# Microcontroller.net
KiCad netlist of a schematic drawn in Altium Designer
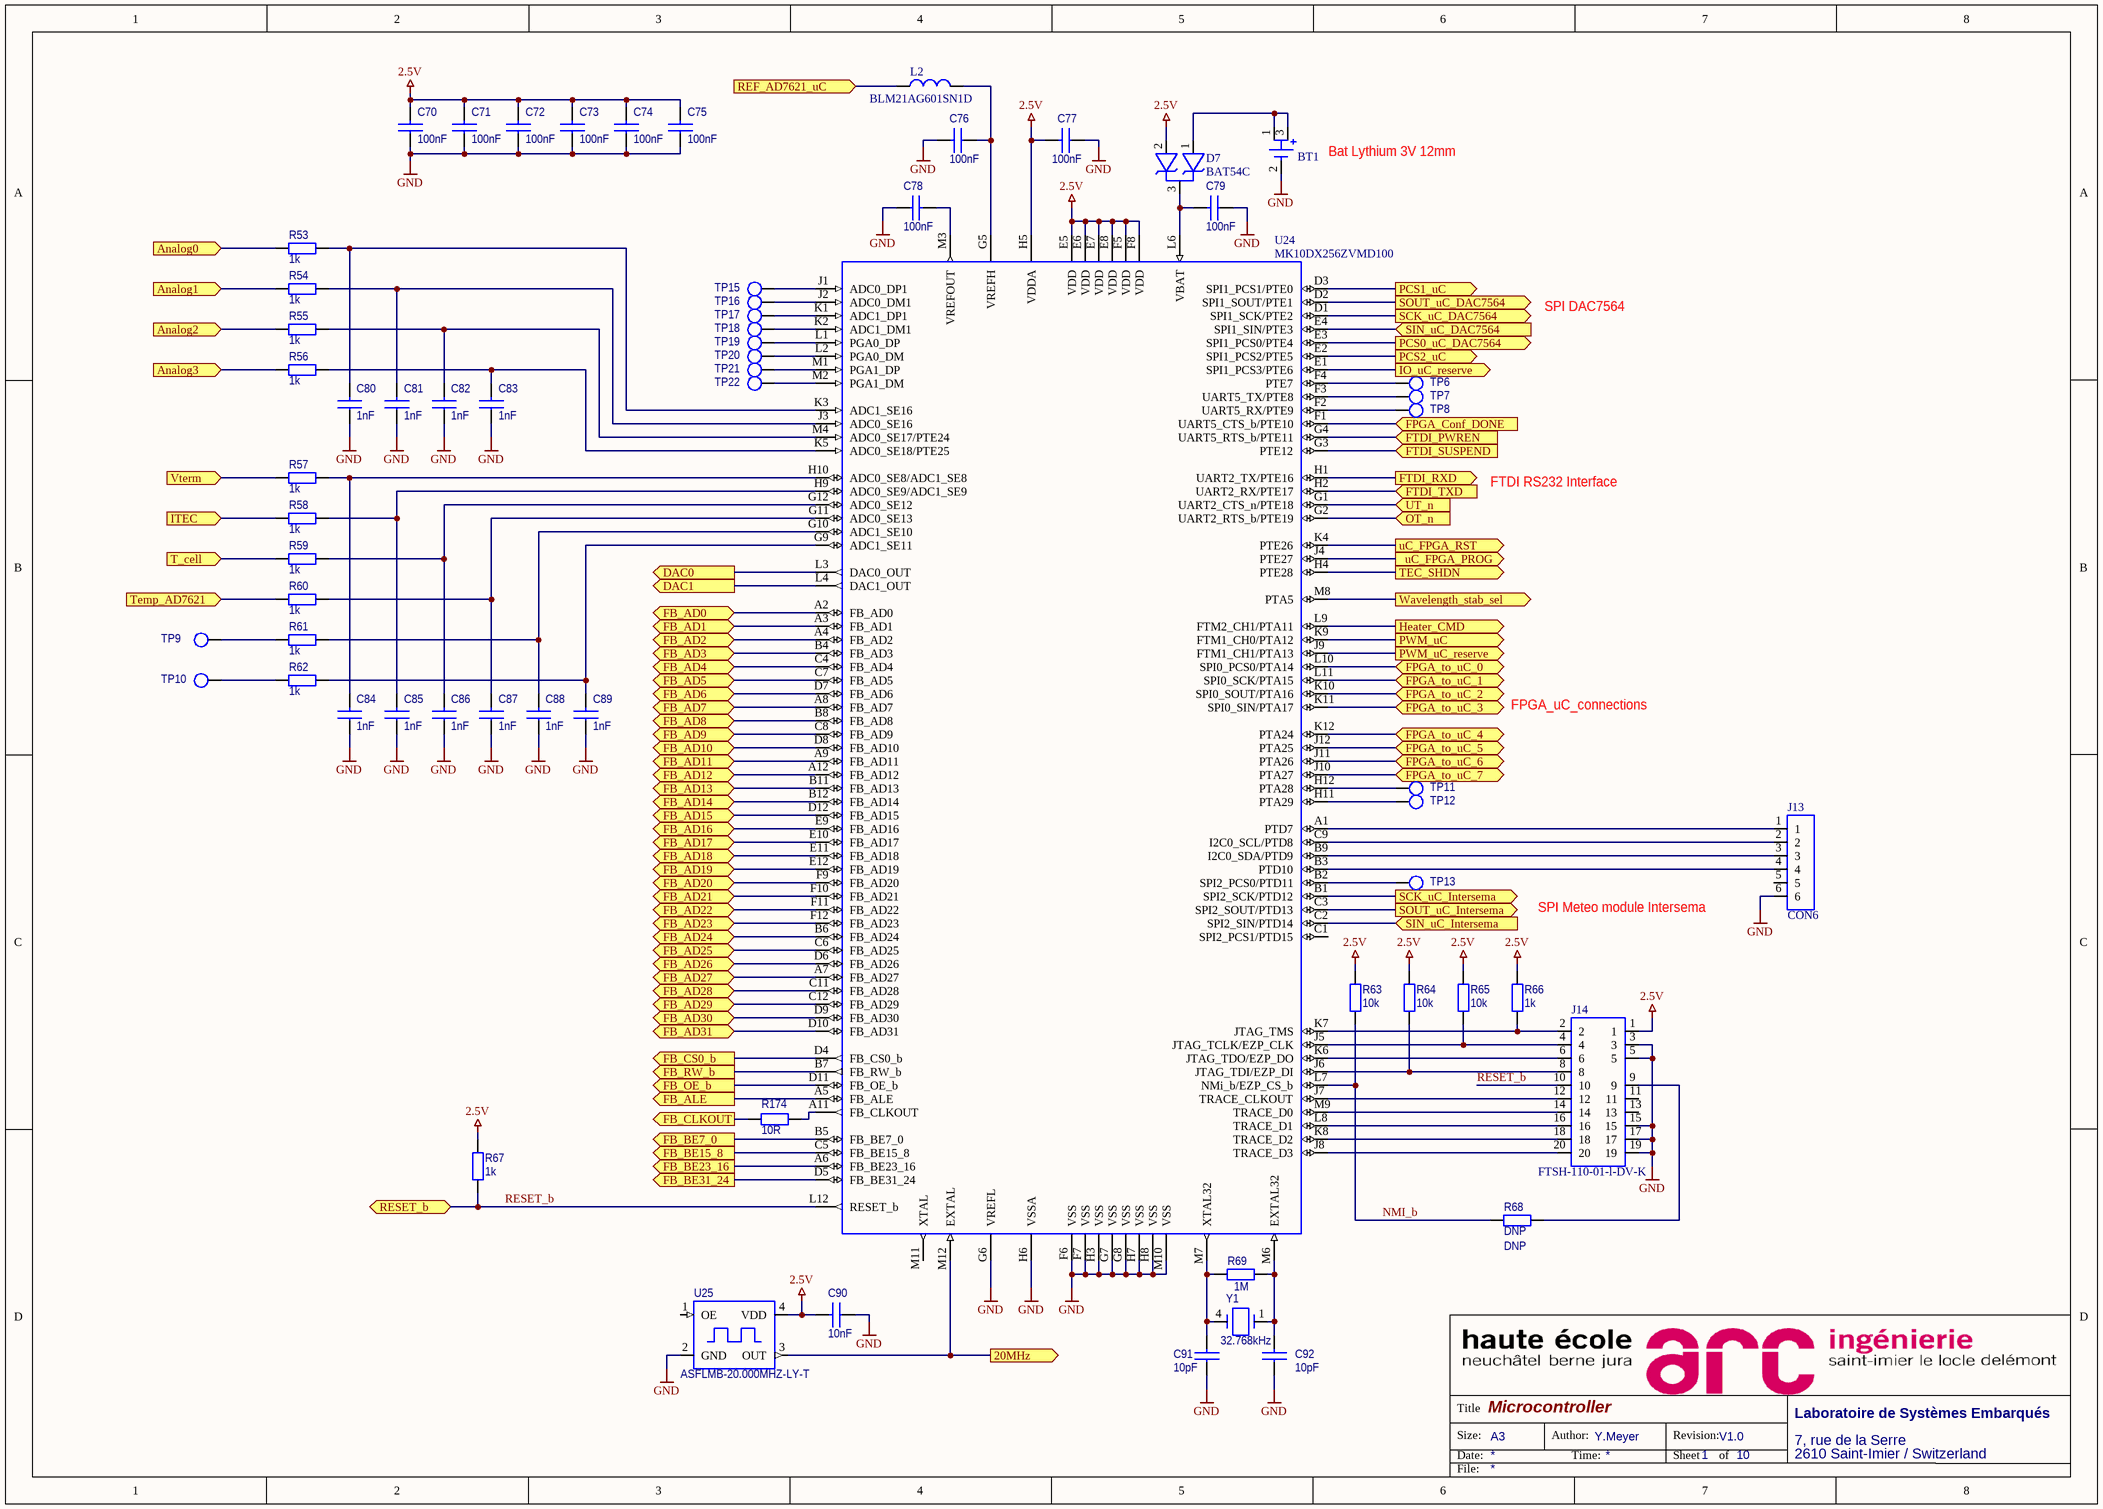
[diagram p0: Microcontroller.SchDoc]

(export (version "E")
  (design (tool "Eeschema 10.0.6"))
  (components
    (comp (ref "BT1")
      (value "3000TR")
      (footprint "3000TR")
      (description "HOLDER BATTERY COIN 12MM DIA SMD")
      (fields (field (name "MANUFACTURER") "Keystone Electronics"))
      (libsource (lib "EISI") (part "BAT_1"))
    )
    (comp (ref "C70")
      (value "100nF")
      (footprint "060301")
      (description "CAP CER 0.1UF 25V 10% X7R 0603")
      (fields (field (name "MANUFACTURER") "TDK Corporation") (field (name "VOLTAGE") "25V"))
      (libsource (lib "EISI") (part "CAPA"))
    )
    (comp (ref "C71")
      (value "100nF")
      (footprint "060301")
      (description "CAP CER 0.1UF 25V 10% X7R 0603")
      (fields (field (name "MANUFACTURER") "TDK Corporation") (field (name "VOLTAGE") "25V"))
      (libsource (lib "EISI") (part "CAPA"))
    )
    (comp (ref "C72")
      (value "100nF")
      (footprint "060301")
      (description "CAP CER 0.1UF 25V 10% X7R 0603")
      (fields (field (name "MANUFACTURER") "TDK Corporation") (field (name "VOLTAGE") "25V"))
      (libsource (lib "EISI") (part "CAPA"))
    )
    (comp (ref "C73")
      (value "100nF")
      (footprint "060301")
      (description "CAP CER 0.1UF 25V 10% X7R 0603")
      (fields (field (name "MANUFACTURER") "TDK Corporation") (field (name "VOLTAGE") "25V"))
      (libsource (lib "EISI") (part "CAPA"))
    )
    (comp (ref "C74")
      (value "100nF")
      (footprint "060301")
      (description "CAP CER 0.1UF 25V 10% X7R 0603")
      (fields (field (name "MANUFACTURER") "TDK Corporation") (field (name "VOLTAGE") "25V"))
      (libsource (lib "EISI") (part "CAPA"))
    )
    (comp (ref "C75")
      (value "100nF")
      (footprint "060301")
      (description "CAP CER 0.1UF 25V 10% X7R 0603")
      (fields (field (name "MANUFACTURER") "TDK Corporation") (field (name "VOLTAGE") "25V"))
      (libsource (lib "EISI") (part "CAPA"))
    )
    (comp (ref "C76")
      (value "100nF")
      (footprint "060301")
      (description "CAP CER 0.1UF 25V 10% X7R 0603")
      (fields (field (name "MANUFACTURER") "TDK Corporation") (field (name "VOLTAGE") "25V"))
      (libsource (lib "EISI") (part "CAPA"))
    )
    (comp (ref "C77")
      (value "100nF")
      (footprint "060301")
      (description "CAP CER 0.1UF 25V 10% X7R 0603")
      (fields (field (name "MANUFACTURER") "TDK Corporation") (field (name "VOLTAGE") "25V"))
      (libsource (lib "EISI") (part "CAPA"))
    )
    (comp (ref "C78")
      (value "100nF")
      (footprint "060301")
      (description "CAP CER 0.1UF 25V 10% X7R 0603")
      (fields (field (name "MANUFACTURER") "TDK Corporation") (field (name "VOLTAGE") "25V"))
      (libsource (lib "EISI") (part "CAPA"))
    )
    (comp (ref "C79")
      (value "100nF")
      (footprint "060301")
      (description "CAP CER 0.1UF 25V 10% X7R 0603")
      (fields (field (name "MANUFACTURER") "TDK Corporation") (field (name "VOLTAGE") "25V"))
      (libsource (lib "EISI") (part "CAPA"))
    )
    (comp (ref "C80")
      (value "1nF")
      (footprint "060301")
      (description "CAP CER 1000PF 50V 10% X7R 0603")
      (fields (field (name "MANUFACTURER") "Murata"))
      (libsource (lib "EISI") (part "CAPA"))
    )
    (comp (ref "C81")
      (value "1nF")
      (footprint "060301")
      (description "CAP CER 1000PF 50V 10% X7R 0603")
      (fields (field (name "MANUFACTURER") "Murata"))
      (libsource (lib "EISI") (part "CAPA"))
    )
    (comp (ref "C82")
      (value "1nF")
      (footprint "060301")
      (description "CAP CER 1000PF 50V 10% X7R 0603")
      (fields (field (name "MANUFACTURER") "Murata"))
      (libsource (lib "EISI") (part "CAPA"))
    )
    (comp (ref "C83")
      (value "1nF")
      (footprint "060301")
      (description "CAP CER 1000PF 50V 10% X7R 0603")
      (fields (field (name "MANUFACTURER") "Murata"))
      (libsource (lib "EISI") (part "CAPA"))
    )
    (comp (ref "C84")
      (value "1nF")
      (footprint "060301")
      (description "CAP CER 1000PF 50V 10% X7R 0603")
      (fields (field (name "MANUFACTURER") "Murata"))
      (libsource (lib "EISI") (part "CAPA"))
    )
    (comp (ref "C85")
      (value "1nF")
      (footprint "060301")
      (description "CAP CER 1000PF 50V 10% X7R 0603")
      (fields (field (name "MANUFACTURER") "Murata"))
      (libsource (lib "EISI") (part "CAPA"))
    )
    (comp (ref "C86")
      (value "1nF")
      (footprint "060301")
      (description "CAP CER 1000PF 50V 10% X7R 0603")
      (fields (field (name "MANUFACTURER") "Murata"))
      (libsource (lib "EISI") (part "CAPA"))
    )
    (comp (ref "C87")
      (value "1nF")
      (footprint "060301")
      (description "CAP CER 1000PF 50V 10% X7R 0603")
      (fields (field (name "MANUFACTURER") "Murata"))
      (libsource (lib "EISI") (part "CAPA"))
    )
    (comp (ref "C88")
      (value "1nF")
      (footprint "060301")
      (description "CAP CER 1000PF 50V 10% X7R 0603")
      (fields (field (name "MANUFACTURER") "Murata"))
      (libsource (lib "EISI") (part "CAPA"))
    )
    (comp (ref "C89")
      (value "1nF")
      (footprint "060301")
      (description "CAP CER 1000PF 50V 10% X7R 0603")
      (fields (field (name "MANUFACTURER") "Murata"))
      (libsource (lib "EISI") (part "CAPA"))
    )
    (comp (ref "C90")
      (value "10nF")
      (footprint "060301")
      (description "CAP CER 10000PF 50V 10% X7R 0")
      (fields (field (name "MANUFACTURER") "EPCOS Inc"))
      (libsource (lib "EISI") (part "CAPA"))
    )
    (comp (ref "C91")
      (value "10pF")
      (footprint "060301")
      (description "CAP CER 10PF 50V 5% NP0 0603")
      (fields (field (name "VOLTAGE") "50V") (field (name "MANUFACTURER") "Kemet"))
      (libsource (lib "EISI") (part "CAPA"))
    )
    (comp (ref "C92")
      (value "10pF")
      (footprint "060301")
      (description "CAP CER 10PF 50V 5% NP0 0603")
      (fields (field (name "VOLTAGE") "50V") (field (name "MANUFACTURER") "Kemet"))
      (libsource (lib "EISI") (part "CAPA"))
    )
    (comp (ref "D7")
      (value "BAT54C")
      (footprint "SOT2301")
      (description "DIODE SCHTTKY CC 200MA 30V SOT23")
      (fields (field (name "MANUFACTURER") "Comchip Technology"))
      (libsource (lib "EISI") (part "BAT54C"))
    )
    (comp (ref "J13")
      (value "CON6")
      (footprint "J106A101")
      (description "Barette 6 pin")
      (libsource (lib "EISI") (part "CON6"))
    )
    (comp (ref "J14")
      (value "FTSH-110-01-l-DV-K")
      (footprint "FTSH-110-01-X-DV-EJ")
      (description "CONN UNSHROUDED HDR 20POS .05\"")
      (fields (field (name "MANUFACTURER") "Samtec Inc"))
      (libsource (lib "EISI") (part "CON20_JTAG"))
    )
    (comp (ref "L2")
      (value "BLM21AG601SN1D")
      (footprint "080501")
      (description "FERRITE CHIP 600 OHM 200MA 0805")
      (fields (field (name "MANUFACTURER") "Murata Electronics"))
      (libsource (lib "EISI") (part "Ferrite Bead"))
    )
    (comp (ref "R53")
      (value "1k")
      (footprint "060301")
      (description "RES 1.00K OHM 1/10W 1% 0603 SMD")
      (fields (field (name "MANUFACTURER") "Yageo"))
      (libsource (lib "EISI") (part "RES"))
    )
    (comp (ref "R54")
      (value "1k")
      (footprint "060301")
      (description "RES 1.00K OHM 1/10W 1% 0603 SMD")
      (fields (field (name "MANUFACTURER") "Yageo"))
      (libsource (lib "EISI") (part "RES"))
    )
    (comp (ref "R55")
      (value "1k")
      (footprint "060301")
      (description "RES 1.00K OHM 1/10W 1% 0603 SMD")
      (fields (field (name "MANUFACTURER") "Yageo"))
      (libsource (lib "EISI") (part "RES"))
    )
    (comp (ref "R56")
      (value "1k")
      (footprint "060301")
      (description "RES 1.00K OHM 1/10W 1% 0603 SMD")
      (fields (field (name "MANUFACTURER") "Yageo"))
      (libsource (lib "EISI") (part "RES"))
    )
    (comp (ref "R57")
      (value "1k")
      (footprint "060301")
      (description "RES 1.00K OHM 1/10W 1% 0603 SMD")
      (fields (field (name "MANUFACTURER") "Yageo"))
      (libsource (lib "EISI") (part "RES"))
    )
    (comp (ref "R58")
      (value "1k")
      (footprint "060301")
      (description "RES 1.00K OHM 1/10W 1% 0603 SMD")
      (fields (field (name "MANUFACTURER") "Yageo"))
      (libsource (lib "EISI") (part "RES"))
    )
    (comp (ref "R59")
      (value "1k")
      (footprint "060301")
      (description "RES 1.00K OHM 1/10W 1% 0603 SMD")
      (fields (field (name "MANUFACTURER") "Yageo"))
      (libsource (lib "EISI") (part "RES"))
    )
    (comp (ref "R60")
      (value "1k")
      (footprint "060301")
      (description "RES 1.00K OHM 1/10W 1% 0603 SMD")
      (fields (field (name "MANUFACTURER") "Yageo"))
      (libsource (lib "EISI") (part "RES"))
    )
    (comp (ref "R61")
      (value "1k")
      (footprint "060301")
      (description "RES 1.00K OHM 1/10W 1% 0603 SMD")
      (fields (field (name "MANUFACTURER") "Yageo"))
      (libsource (lib "EISI") (part "RES"))
    )
    (comp (ref "R62")
      (value "1k")
      (footprint "060301")
      (description "RES 1.00K OHM 1/10W 1% 0603 SMD")
      (fields (field (name "MANUFACTURER") "Yageo"))
      (libsource (lib "EISI") (part "RES"))
    )
    (comp (ref "R63")
      (value "10k")
      (footprint "060301")
      (description "RES 10.0K OHM 1/10W 1% 0603 SMD")
      (fields (field (name "MANUFACTURER") "Yageo"))
      (libsource (lib "") (part "RES_1"))
    )
    (comp (ref "R64")
      (value "10k")
      (footprint "060301")
      (description "RES 10.0K OHM 1/10W 1% 0603 SMD")
      (fields (field (name "MANUFACTURER") "Yageo"))
      (libsource (lib "") (part "RES_1"))
    )
    (comp (ref "R65")
      (value "10k")
      (footprint "060301")
      (description "RES 10.0K OHM 1/10W 1% 0603 SMD")
      (fields (field (name "MANUFACTURER") "Yageo"))
      (libsource (lib "") (part "RES_1"))
    )
    (comp (ref "R66")
      (value "1k")
      (footprint "060301")
      (description "RES 1.00K OHM 1/10W 1% 0603 SMD")
      (fields (field (name "MANUFACTURER") "Yageo"))
      (libsource (lib "") (part "RES_1"))
    )
    (comp (ref "R67")
      (value "1k")
      (footprint "060301")
      (description "RES 1.00K OHM 1/10W 1% 0603 SMD")
      (fields (field (name "MANUFACTURER") "Yageo"))
      (libsource (lib "") (part "RES_1"))
    )
    (comp (ref "R68")
      (value "DNP")
      (footprint "060301")
      (description "RES 0.0 OHM 1/10W 0603 SMD")
      (fields (field (name "DNP") "DNP") (field (name "MANUFACTURER") "Yageo"))
      (libsource (lib "EISI") (part "RES"))
    )
    (comp (ref "R69")
      (value "1M")
      (footprint "060301")
      (description "RES 1.00M OHM 1/10W 1% 0603 SMD")
      (fields (field (name "MANUFACTURER") "Yageo"))
      (libsource (lib "EISI") (part "RES"))
    )
    (comp (ref "R174")
      (value "10R")
      (footprint "060301")
      (description "RES 10.0 OHM 1/10W 1% 0603 SMD")
      (fields (field (name "MANUFACTURER") "Yageo"))
      (libsource (lib "EISI") (part "RES"))
    )
    (comp (ref "TP6") (value "Test point") (footprint "TP_SMD_06mm") (libsource (lib "EISI") (part "TP")))
    (comp (ref "TP7") (value "Test point") (footprint "TP_SMD_06mm") (libsource (lib "EISI") (part "TP")))
    (comp (ref "TP8") (value "Test point") (footprint "TP_SMD_06mm") (libsource (lib "EISI") (part "TP")))
    (comp (ref "TP9") (value "Test point") (footprint "TP_SMD_06mm") (libsource (lib "EISI") (part "TP")))
    (comp (ref "TP10") (value "Test point") (footprint "TP_SMD_06mm") (libsource (lib "EISI") (part "TP")))
    (comp (ref "TP11") (value "Test point") (footprint "TP_SMD_06mm") (libsource (lib "EISI") (part "TP")))
    (comp (ref "TP12") (value "Test point") (footprint "TP_SMD_06mm") (libsource (lib "EISI") (part "TP")))
    (comp (ref "TP13") (value "Test point") (footprint "TP_SMD_06mm") (libsource (lib "EISI") (part "TP")))
    (comp (ref "TP15") (value "Test point") (footprint "TP_SMD_06mm") (libsource (lib "EISI") (part "TP")))
    (comp (ref "TP16") (value "Test point") (footprint "TP_SMD_06mm") (libsource (lib "EISI") (part "TP")))
    (comp (ref "TP17") (value "Test point") (footprint "TP_SMD_06mm") (libsource (lib "EISI") (part "TP")))
    (comp (ref "TP18") (value "Test point") (footprint "TP_SMD_06mm") (libsource (lib "EISI") (part "TP")))
    (comp (ref "TP19") (value "Test point") (footprint "TP_SMD_06mm") (libsource (lib "EISI") (part "TP")))
    (comp (ref "TP20") (value "Test point") (footprint "TP_SMD_06mm") (libsource (lib "EISI") (part "TP")))
    (comp (ref "TP21") (value "Test point") (footprint "TP_SMD_06mm") (libsource (lib "EISI") (part "TP")))
    (comp (ref "TP22") (value "Test point") (footprint "TP_SMD_06mm") (libsource (lib "EISI") (part "TP")))
    (comp (ref "U24")
      (value "MK10DX256ZVMD100")
      (footprint "MAPBGA144")
      (description "IC ARM CORTEX MCU 256K 144-MAP")
      (fields (field (name "MANUFACTURER") "Freescale Semiconductor"))
      (libsource (lib "EISI") (part "MK10X256VMD100"))
    )
    (comp (ref "U25")
      (value "ASFLMB-20.000MHZ-LY-T")
      (footprint "OSC05")
      (description "OSC MEMS 20.000 MHZ SMD")
      (fields (field (name "MANUFACTURER") "Abracon Corporation"))
      (libsource (lib "EISI") (part "Oscillateur"))
    )
    (comp (ref "Y1")
      (value "32.768kHz")
      (description "CRYSTAL 32.768 KHZ 12.5PF SMD")
      (fields (field (name "MANUFACTURER") "ECS Inc") (field (name "Comment") "ECS-.327-12.5-17X-C-TR"))
      (libsource (lib "*") (part "Crystal_32"))
    )
  )
  (nets
    (net (code "1") (name "/20MHz") (class "Default")
      (node (ref "U24") (pin "M12") (pinfunction "EXTAL_M12") (pintype "input"))
      (node (ref "U25") (pin "3") (pinfunction "OUT_3") (pintype "output"))
    )
    (net (code "2") (name "/Analog0") (class "Default")
      (node (ref "R53") (pin "1") (pinfunction "1_1") (pintype "passive"))
    )
    (net (code "3") (name "/Analog1") (class "Default")
      (node (ref "R54") (pin "1") (pinfunction "1_1") (pintype "passive"))
    )
    (net (code "4") (name "/Analog2") (class "Default")
      (node (ref "R55") (pin "1") (pinfunction "1_1") (pintype "passive"))
    )
    (net (code "5") (name "/Analog3") (class "Default")
      (node (ref "R56") (pin "1") (pinfunction "1_1") (pintype "passive"))
    )
    (net (code "6") (name "/DAC0") (class "Default")
      (node (ref "U24") (pin "L3") (pinfunction "DAC0_OUT_L3") (pintype "output"))
    )
    (net (code "7") (name "/DAC1") (class "Default")
      (node (ref "U24") (pin "L4") (pinfunction "DAC1_OUT_L4") (pintype "output"))
    )
    (net (code "8") (name "/FB_AD0") (class "Default")
      (node (ref "U24") (pin "A2") (pinfunction "FB_AD0_A2") (pintype "bidirectional"))
    )
    (net (code "9") (name "/FB_AD1") (class "Default")
      (node (ref "U24") (pin "A3") (pinfunction "FB_AD1_A3") (pintype "bidirectional"))
    )
    (net (code "10") (name "/FB_AD2") (class "Default")
      (node (ref "U24") (pin "A4") (pinfunction "FB_AD2_A4") (pintype "bidirectional"))
    )
    (net (code "11") (name "/FB_AD3") (class "Default")
      (node (ref "U24") (pin "B4") (pinfunction "FB_AD3_B4") (pintype "bidirectional"))
    )
    (net (code "12") (name "/FB_AD4") (class "Default")
      (node (ref "U24") (pin "C4") (pinfunction "FB_AD4_C4") (pintype "bidirectional"))
    )
    (net (code "13") (name "/FB_AD5") (class "Default")
      (node (ref "U24") (pin "C7") (pinfunction "FB_AD5_C7") (pintype "bidirectional"))
    )
    (net (code "14") (name "/FB_AD6") (class "Default")
      (node (ref "U24") (pin "D7") (pinfunction "FB_AD6_D7") (pintype "bidirectional"))
    )
    (net (code "15") (name "/FB_AD7") (class "Default")
      (node (ref "U24") (pin "A8") (pinfunction "FB_AD7_A8") (pintype "bidirectional"))
    )
    (net (code "16") (name "/FB_AD8") (class "Default")
      (node (ref "U24") (pin "B8") (pinfunction "FB_AD8_B8") (pintype "bidirectional"))
    )
    (net (code "17") (name "/FB_AD9") (class "Default")
      (node (ref "U24") (pin "C8") (pinfunction "FB_AD9_C8") (pintype "bidirectional"))
    )
    (net (code "18") (name "/FB_AD10") (class "Default")
      (node (ref "U24") (pin "D8") (pinfunction "FB_AD10_D8") (pintype "bidirectional"))
    )
    (net (code "19") (name "/FB_AD11") (class "Default")
      (node (ref "U24") (pin "A9") (pinfunction "FB_AD11_A9") (pintype "bidirectional"))
    )
    (net (code "20") (name "/FB_AD12") (class "Default")
      (node (ref "U24") (pin "A12") (pinfunction "FB_AD12_A12") (pintype "bidirectional"))
    )
    (net (code "21") (name "/FB_AD13") (class "Default")
      (node (ref "U24") (pin "B11") (pinfunction "FB_AD13_B11") (pintype "bidirectional"))
    )
    (net (code "22") (name "/FB_AD14") (class "Default")
      (node (ref "U24") (pin "B12") (pinfunction "FB_AD14_B12") (pintype "bidirectional"))
    )
    (net (code "23") (name "/FB_AD15") (class "Default")
      (node (ref "U24") (pin "D12") (pinfunction "FB_AD15_D12") (pintype "bidirectional"))
    )
    (net (code "24") (name "/FB_AD16") (class "Default")
      (node (ref "U24") (pin "E9") (pinfunction "FB_AD16_E9") (pintype "bidirectional"))
    )
    (net (code "25") (name "/FB_AD17") (class "Default")
      (node (ref "U24") (pin "E10") (pinfunction "FB_AD17_E10") (pintype "bidirectional"))
    )
    (net (code "26") (name "/FB_AD18") (class "Default")
      (node (ref "U24") (pin "E11") (pinfunction "FB_AD18_E11") (pintype "bidirectional"))
    )
    (net (code "27") (name "/FB_AD19") (class "Default")
      (node (ref "U24") (pin "E12") (pinfunction "FB_AD19_E12") (pintype "bidirectional"))
    )
    (net (code "28") (name "/FB_AD20") (class "Default")
      (node (ref "U24") (pin "F9") (pinfunction "FB_AD20_F9") (pintype "bidirectional"))
    )
    (net (code "29") (name "/FB_AD21") (class "Default")
      (node (ref "U24") (pin "F10") (pinfunction "FB_AD21_F10") (pintype "bidirectional"))
    )
    (net (code "30") (name "/FB_AD22") (class "Default")
      (node (ref "U24") (pin "F11") (pinfunction "FB_AD22_F11") (pintype "bidirectional"))
    )
    (net (code "31") (name "/FB_AD23") (class "Default")
      (node (ref "U24") (pin "F12") (pinfunction "FB_AD23_F12") (pintype "bidirectional"))
    )
    (net (code "32") (name "/FB_AD24") (class "Default")
      (node (ref "U24") (pin "B6") (pinfunction "FB_AD24_B6") (pintype "bidirectional"))
    )
    (net (code "33") (name "/FB_AD25") (class "Default")
      (node (ref "U24") (pin "C6") (pinfunction "FB_AD25_C6") (pintype "bidirectional"))
    )
    (net (code "34") (name "/FB_AD26") (class "Default")
      (node (ref "U24") (pin "D6") (pinfunction "FB_AD26_D6") (pintype "bidirectional"))
    )
    (net (code "35") (name "/FB_AD27") (class "Default")
      (node (ref "U24") (pin "A7") (pinfunction "FB_AD27_A7") (pintype "bidirectional"))
    )
    (net (code "36") (name "/FB_AD28") (class "Default")
      (node (ref "U24") (pin "C11") (pinfunction "FB_AD28_C11") (pintype "bidirectional"))
    )
    (net (code "37") (name "/FB_AD29") (class "Default")
      (node (ref "U24") (pin "C12") (pinfunction "FB_AD29_C12") (pintype "bidirectional"))
    )
    (net (code "38") (name "/FB_AD30") (class "Default")
      (node (ref "U24") (pin "D9") (pinfunction "FB_AD30_D9") (pintype "bidirectional"))
    )
    (net (code "39") (name "/FB_AD31") (class "Default")
      (node (ref "U24") (pin "D10") (pinfunction "FB_AD31_D10") (pintype "bidirectional"))
    )
    (net (code "40") (name "/FB_ALE") (class "Default")
      (node (ref "U24") (pin "A5") (pinfunction "FB_ALE_A5") (pintype "bidirectional"))
    )
    (net (code "41") (name "/FB_BE7_0") (class "Default")
      (node (ref "U24") (pin "B5") (pinfunction "FB_BE7_0_B5") (pintype "bidirectional"))
    )
    (net (code "42") (name "/FB_BE15_8") (class "Default")
      (node (ref "U24") (pin "C5") (pinfunction "FB_BE15_8_C5") (pintype "bidirectional"))
    )
    (net (code "43") (name "/FB_BE23_16") (class "Default")
      (node (ref "U24") (pin "A6") (pinfunction "FB_BE23_16_A6") (pintype "bidirectional"))
    )
    (net (code "44") (name "/FB_BE31_24") (class "Default")
      (node (ref "U24") (pin "D5") (pinfunction "FB_BE31_24_D5") (pintype "bidirectional"))
    )
    (net (code "45") (name "/FB_CLKOUT") (class "Default")
      (node (ref "R174") (pin "1") (pinfunction "1_1") (pintype "passive"))
    )
    (net (code "46") (name "/FB_CS0_b") (class "Default")
      (node (ref "U24") (pin "D4") (pinfunction "FB_CS0_b_D4") (pintype "output"))
    )
    (net (code "47") (name "/FB_OE_b") (class "Default")
      (node (ref "U24") (pin "D11") (pinfunction "FB_OE_b_D11") (pintype "bidirectional"))
    )
    (net (code "48") (name "/FB_RW_b") (class "Default")
      (node (ref "U24") (pin "B7") (pinfunction "FB_RW_b_B7") (pintype "output"))
    )
    (net (code "49") (name "/FPGA_Conf_DONE") (class "Default")
      (node (ref "U24") (pin "F1") (pinfunction "UART5_CTS_b/PTE10_F1") (pintype "bidirectional"))
    )
    (net (code "50") (name "/FPGA_to_uC_0") (class "Default")
      (node (ref "U24") (pin "L10") (pinfunction "SPI0_PCS0/PTA14_L10") (pintype "bidirectional"))
    )
    (net (code "51") (name "/FPGA_to_uC_1") (class "Default")
      (node (ref "U24") (pin "L11") (pinfunction "SPI0_SCK/PTA15_L11") (pintype "bidirectional"))
    )
    (net (code "52") (name "/FPGA_to_uC_2") (class "Default")
      (node (ref "U24") (pin "K10") (pinfunction "SPI0_SOUT/PTA16_K10") (pintype "bidirectional"))
    )
    (net (code "53") (name "/FPGA_to_uC_3") (class "Default")
      (node (ref "U24") (pin "K11") (pinfunction "SPI0_SIN/PTA17_K11") (pintype "bidirectional"))
    )
    (net (code "54") (name "/FPGA_to_uC_4") (class "Default")
      (node (ref "U24") (pin "K12") (pinfunction "PTA24_K12") (pintype "bidirectional"))
    )
    (net (code "55") (name "/FPGA_to_uC_5") (class "Default")
      (node (ref "U24") (pin "J12") (pinfunction "PTA25_J12") (pintype "bidirectional"))
    )
    (net (code "56") (name "/FPGA_to_uC_6") (class "Default")
      (node (ref "U24") (pin "J11") (pinfunction "PTA26_J11") (pintype "bidirectional"))
    )
    (net (code "57") (name "/FPGA_to_uC_7") (class "Default")
      (node (ref "U24") (pin "J10") (pinfunction "PTA27_J10") (pintype "bidirectional"))
    )
    (net (code "58") (name "/FTDI_PWREN") (class "Default")
      (node (ref "U24") (pin "G4") (pinfunction "UART5_RTS_b/PTE11_G4") (pintype "bidirectional"))
    )
    (net (code "59") (name "/FTDI_RXD") (class "Default")
      (node (ref "U24") (pin "H1") (pinfunction "UART2_TX/PTE16_H1") (pintype "bidirectional"))
    )
    (net (code "60") (name "/FTDI_SUSPEND") (class "Default")
      (node (ref "U24") (pin "G3") (pinfunction "PTE12_G3") (pintype "bidirectional"))
    )
    (net (code "61") (name "/FTDI_TXD") (class "Default")
      (node (ref "U24") (pin "H2") (pinfunction "UART2_RX/PTE17_H2") (pintype "bidirectional"))
    )
    (net (code "62") (name "/Heater_CMD") (class "Default")
      (node (ref "U24") (pin "L9") (pinfunction "FTM2_CH1/PTA11_L9") (pintype "bidirectional"))
    )
    (net (code "63") (name "/IO_uC_reserve") (class "Default")
      (node (ref "U24") (pin "E1") (pinfunction "SPI1_PCS3/PTE6_E1") (pintype "bidirectional"))
    )
    (net (code "64") (name "/ITEC") (class "Default")
      (node (ref "R58") (pin "1") (pinfunction "1_1") (pintype "passive"))
    )
    (net (code "65") (name "/NMI_b") (class "Default")
      (node (ref "R63") (pin "2") (pinfunction "2_2") (pintype "passive"))
      (node (ref "R68") (pin "1") (pinfunction "1_1") (pintype "passive"))
      (node (ref "U24") (pin "L7") (pinfunction "NMi_b/EZP_CS_b_L7") (pintype "bidirectional"))
    )
    (net (code "66") (name "/OT_n") (class "Default")
      (node (ref "U24") (pin "G2") (pinfunction "UART2_RTS_b/PTE19_G2") (pintype "bidirectional"))
    )
    (net (code "67") (name "/PCS0_uC_DAC7564") (class "Default")
      (node (ref "U24") (pin "E3") (pinfunction "SPI1_PCS0/PTE4_E3") (pintype "bidirectional"))
    )
    (net (code "68") (name "/PCS1_uC") (class "Default")
      (node (ref "U24") (pin "D3") (pinfunction "SPI1_PCS1/PTE0_D3") (pintype "bidirectional"))
    )
    (net (code "69") (name "/PCS2_uC") (class "Default")
      (node (ref "U24") (pin "E2") (pinfunction "SPI1_PCS2/PTE5_E2") (pintype "bidirectional"))
    )
    (net (code "70") (name "/PWM_uC") (class "Default")
      (node (ref "U24") (pin "K9") (pinfunction "FTM1_CH0/PTA12_K9") (pintype "bidirectional"))
    )
    (net (code "71") (name "/PWM_uC_reserve") (class "Default")
      (node (ref "U24") (pin "J9") (pinfunction "FTM1_CH1/PTA13_J9") (pintype "bidirectional"))
    )
    (net (code "72") (name "/REF_AD7621_uC") (class "Default")
      (node (ref "L2") (pin "1") (pinfunction "1_1") (pintype "passive"))
    )
    (net (code "73") (name "/RESET_b") (class "Default")
      (node (ref "J14") (pin "10") (pinfunction "10_10") (pintype "passive"))
      (node (ref "R67") (pin "2") (pinfunction "2_2") (pintype "passive"))
      (node (ref "U24") (pin "L12") (pinfunction "RESET_b_L12") (pintype "output"))
    )
    (net (code "74") (name "/SCK_uC_DAC7564") (class "Default")
      (node (ref "U24") (pin "D1") (pinfunction "SPI1_SCK/PTE2_D1") (pintype "bidirectional"))
    )
    (net (code "75") (name "/SCK_uC_Intersema") (class "Default")
      (node (ref "U24") (pin "B1") (pinfunction "SPI2_SCK/PTD12_B1") (pintype "bidirectional"))
    )
    (net (code "76") (name "/SIN_uC_DAC7564") (class "Default")
      (node (ref "U24") (pin "E4") (pinfunction "SPI1_SIN/PTE3_E4") (pintype "bidirectional"))
    )
    (net (code "77") (name "/SIN_uC_Intersema") (class "Default")
      (node (ref "U24") (pin "C2") (pinfunction "SPI2_SIN/PTD14_C2") (pintype "bidirectional"))
    )
    (net (code "78") (name "/SOUT_uC_DAC7564") (class "Default")
      (node (ref "U24") (pin "D2") (pinfunction "SPI1_SOUT/PTE1_D2") (pintype "bidirectional"))
    )
    (net (code "79") (name "/SOUT_uC_Intersema") (class "Default")
      (node (ref "U24") (pin "C3") (pinfunction "SPI2_SOUT/PTD13_C3") (pintype "bidirectional"))
    )
    (net (code "80") (name "/TEC_SHDN") (class "Default")
      (node (ref "U24") (pin "H4") (pinfunction "PTE28_H4") (pintype "bidirectional"))
    )
    (net (code "81") (name "/T_cell") (class "Default")
      (node (ref "R59") (pin "1") (pinfunction "1_1") (pintype "passive"))
    )
    (net (code "82") (name "/Temp_AD7621") (class "Default")
      (node (ref "R60") (pin "1") (pinfunction "1_1") (pintype "passive"))
    )
    (net (code "83") (name "/UT_n") (class "Default")
      (node (ref "U24") (pin "G1") (pinfunction "UART2_CTS_n/PTE18_G1") (pintype "bidirectional"))
    )
    (net (code "84") (name "/Vterm") (class "Default")
      (node (ref "R57") (pin "1") (pinfunction "1_1") (pintype "passive"))
    )
    (net (code "85") (name "/Wavelength_stab_sel") (class "Default")
      (node (ref "U24") (pin "M8") (pinfunction "PTA5_M8") (pintype "bidirectional"))
    )
    (net (code "86") (name "/uC_FPGA_PROG") (class "Default")
      (node (ref "U24") (pin "J4") (pinfunction "PTE27_J4") (pintype "bidirectional"))
    )
    (net (code "87") (name "/uC_FPGA_RST") (class "Default")
      (node (ref "U24") (pin "K4") (pinfunction "PTE26_K4") (pintype "bidirectional"))
    )
    (net (code "88") (name "2.5V") (class "Default")
      (node (ref "C70") (pin "2") (pinfunction "2_2") (pintype "passive"))
      (node (ref "C71") (pin "2") (pinfunction "2_2") (pintype "passive"))
      (node (ref "C72") (pin "2") (pinfunction "2_2") (pintype "passive"))
      (node (ref "C73") (pin "2") (pinfunction "2_2") (pintype "passive"))
      (node (ref "C74") (pin "2") (pinfunction "2_2") (pintype "passive"))
      (node (ref "C75") (pin "2") (pinfunction "2_2") (pintype "passive"))
      (node (ref "C77") (pin "2") (pinfunction "2_2") (pintype "passive"))
      (node (ref "C90") (pin "2") (pinfunction "2_2") (pintype "passive"))
      (node (ref "D7") (pin "2") (pinfunction "C2_2") (pintype "passive"))
      (node (ref "J14") (pin "1") (pinfunction "1_1") (pintype "passive"))
      (node (ref "R63") (pin "1") (pinfunction "1_1") (pintype "passive"))
      (node (ref "R64") (pin "1") (pinfunction "1_1") (pintype "passive"))
      (node (ref "R65") (pin "1") (pinfunction "1_1") (pintype "passive"))
      (node (ref "R66") (pin "1") (pinfunction "1_1") (pintype "passive"))
      (node (ref "R67") (pin "1") (pinfunction "1_1") (pintype "passive"))
      (node (ref "U24") (pin "E5") (pinfunction "VDD_E5") (pintype "power_in"))
      (node (ref "U24") (pin "E6") (pinfunction "VDD_E6") (pintype "power_in"))
      (node (ref "U24") (pin "E7") (pinfunction "VDD_E7") (pintype "power_in"))
      (node (ref "U24") (pin "E8") (pinfunction "VDD_E8") (pintype "power_in"))
      (node (ref "U24") (pin "F5") (pinfunction "VDD_F5") (pintype "power_in"))
      (node (ref "U24") (pin "F8") (pinfunction "VDD_F8") (pintype "power_in"))
      (node (ref "U24") (pin "H5") (pinfunction "VDDA_H5") (pintype "power_in"))
      (node (ref "U25") (pin "4") (pinfunction "VDD_4") (pintype "power_in"))
    )
    (net (code "89") (name "GND") (class "Default")
      (node (ref "BT1") (pin "2") (pinfunction "C_2") (pintype "passive"))
      (node (ref "C70") (pin "1") (pinfunction "1_1") (pintype "passive"))
      (node (ref "C71") (pin "1") (pinfunction "1_1") (pintype "passive"))
      (node (ref "C72") (pin "1") (pinfunction "1_1") (pintype "passive"))
      (node (ref "C73") (pin "1") (pinfunction "1_1") (pintype "passive"))
      (node (ref "C74") (pin "1") (pinfunction "1_1") (pintype "passive"))
      (node (ref "C75") (pin "1") (pinfunction "1_1") (pintype "passive"))
      (node (ref "C76") (pin "2") (pinfunction "2_2") (pintype "passive"))
      (node (ref "C77") (pin "1") (pinfunction "1_1") (pintype "passive"))
      (node (ref "C78") (pin "1") (pinfunction "1_1") (pintype "passive"))
      (node (ref "C79") (pin "1") (pinfunction "1_1") (pintype "passive"))
      (node (ref "C80") (pin "1") (pinfunction "1_1") (pintype "passive"))
      (node (ref "C81") (pin "1") (pinfunction "1_1") (pintype "passive"))
      (node (ref "C82") (pin "1") (pinfunction "1_1") (pintype "passive"))
      (node (ref "C83") (pin "1") (pinfunction "1_1") (pintype "passive"))
      (node (ref "C84") (pin "1") (pinfunction "1_1") (pintype "passive"))
      (node (ref "C85") (pin "1") (pinfunction "1_1") (pintype "passive"))
      (node (ref "C86") (pin "1") (pinfunction "1_1") (pintype "passive"))
      (node (ref "C87") (pin "1") (pinfunction "1_1") (pintype "passive"))
      (node (ref "C88") (pin "1") (pinfunction "1_1") (pintype "passive"))
      (node (ref "C89") (pin "1") (pinfunction "1_1") (pintype "passive"))
      (node (ref "C90") (pin "1") (pinfunction "1_1") (pintype "passive"))
      (node (ref "C91") (pin "1") (pinfunction "1_1") (pintype "passive"))
      (node (ref "C92") (pin "1") (pinfunction "1_1") (pintype "passive"))
      (node (ref "J13") (pin "6") (pinfunction "6_6") (pintype "passive"))
      (node (ref "J14") (pin "15") (pinfunction "15_15") (pintype "passive"))
      (node (ref "J14") (pin "17") (pinfunction "17_17") (pintype "passive"))
      (node (ref "J14") (pin "19") (pinfunction "19_19") (pintype "passive"))
      (node (ref "J14") (pin "3") (pinfunction "3_3") (pintype "passive"))
      (node (ref "J14") (pin "5") (pinfunction "5_5") (pintype "passive"))
      (node (ref "U24") (pin "F6") (pinfunction "VSS_F6") (pintype "power_in"))
      (node (ref "U24") (pin "F7") (pinfunction "VSS_F7") (pintype "power_in"))
      (node (ref "U24") (pin "G6") (pinfunction "VREFL_G6") (pintype "passive"))
      (node (ref "U24") (pin "G7") (pinfunction "VSS_G7") (pintype "power_in"))
      (node (ref "U24") (pin "G8") (pinfunction "VSS_G8") (pintype "power_in"))
      (node (ref "U24") (pin "H3") (pinfunction "VSS_H3") (pintype "power_in"))
      (node (ref "U24") (pin "H6") (pinfunction "VSSA_H6") (pintype "power_in"))
      (node (ref "U24") (pin "H7") (pinfunction "VSS_H7") (pintype "power_in"))
      (node (ref "U24") (pin "H8") (pinfunction "VSS_H8") (pintype "power_in"))
      (node (ref "U24") (pin "M10") (pinfunction "VSS_M10") (pintype "power_in"))
      (node (ref "U25") (pin "2") (pinfunction "GND_2") (pintype "power_in"))
    )
    (net (code "90") (name "Net-(BT1-A1)") (class "Default")
      (node (ref "BT1") (pin "1") (pinfunction "A1_1") (pintype "passive"))
      (node (ref "BT1") (pin "3") (pinfunction "A2_3") (pintype "passive"))
      (node (ref "D7") (pin "1") (pinfunction "C1_1") (pintype "passive"))
    )
    (net (code "91") (name "Net-(D7-Anode)") (class "Default")
      (node (ref "C79") (pin "2") (pinfunction "2_2") (pintype "passive"))
      (node (ref "D7") (pin "3") (pinfunction "Anode_3") (pintype "passive"))
      (node (ref "U24") (pin "L6") (pinfunction "VBAT_L6") (pintype "input"))
    )
    (net (code "92") (name "Net-(J14-Pad9)") (class "Default")
      (node (ref "J14") (pin "9") (pinfunction "9_9") (pintype "passive"))
      (node (ref "R68") (pin "2") (pinfunction "2_2") (pintype "passive"))
    )
    (net (code "93") (name "Net-(TP6-TP)") (class "Default")
      (node (ref "TP6") (pin "1") (pinfunction "TP_1") (pintype "passive"))
      (node (ref "U24") (pin "F4") (pinfunction "PTE7_F4") (pintype "bidirectional"))
    )
    (net (code "94") (name "Net-(TP7-TP)") (class "Default")
      (node (ref "TP7") (pin "1") (pinfunction "TP_1") (pintype "passive"))
      (node (ref "U24") (pin "F3") (pinfunction "UART5_TX/PTE8_F3") (pintype "bidirectional"))
    )
    (net (code "95") (name "Net-(TP8-TP)") (class "Default")
      (node (ref "TP8") (pin "1") (pinfunction "TP_1") (pintype "passive"))
      (node (ref "U24") (pin "F2") (pinfunction "UART5_RX/PTE9_F2") (pintype "bidirectional"))
    )
    (net (code "96") (name "Net-(TP9-TP)") (class "Default")
      (node (ref "R61") (pin "1") (pinfunction "1_1") (pintype "passive"))
      (node (ref "TP9") (pin "1") (pinfunction "TP_1") (pintype "passive"))
    )
    (net (code "97") (name "Net-(TP10-TP)") (class "Default")
      (node (ref "R62") (pin "1") (pinfunction "1_1") (pintype "passive"))
      (node (ref "TP10") (pin "1") (pinfunction "TP_1") (pintype "passive"))
    )
    (net (code "98") (name "Net-(TP11-TP)") (class "Default")
      (node (ref "TP11") (pin "1") (pinfunction "TP_1") (pintype "passive"))
      (node (ref "U24") (pin "H12") (pinfunction "PTA28_H12") (pintype "bidirectional"))
    )
    (net (code "99") (name "Net-(TP12-TP)") (class "Default")
      (node (ref "TP12") (pin "1") (pinfunction "TP_1") (pintype "passive"))
      (node (ref "U24") (pin "H11") (pinfunction "PTA29_H11") (pintype "bidirectional"))
    )
    (net (code "100") (name "Net-(TP13-TP)") (class "Default")
      (node (ref "TP13") (pin "1") (pinfunction "TP_1") (pintype "passive"))
      (node (ref "U24") (pin "B2") (pinfunction "SPI2_PCS0/PTD11_B2") (pintype "bidirectional"))
    )
    (net (code "101") (name "Net-(TP15-TP)") (class "Default")
      (node (ref "TP15") (pin "1") (pinfunction "TP_1") (pintype "passive"))
      (node (ref "U24") (pin "J1") (pinfunction "ADC0_DP1_J1") (pintype "input"))
    )
    (net (code "102") (name "Net-(TP16-TP)") (class "Default")
      (node (ref "TP16") (pin "1") (pinfunction "TP_1") (pintype "passive"))
      (node (ref "U24") (pin "J2") (pinfunction "ADC0_DM1_J2") (pintype "input"))
    )
    (net (code "103") (name "Net-(TP17-TP)") (class "Default")
      (node (ref "TP17") (pin "1") (pinfunction "TP_1") (pintype "passive"))
      (node (ref "U24") (pin "K1") (pinfunction "ADC1_DP1_K1") (pintype "input"))
    )
    (net (code "104") (name "Net-(TP18-TP)") (class "Default")
      (node (ref "TP18") (pin "1") (pinfunction "TP_1") (pintype "passive"))
      (node (ref "U24") (pin "K2") (pinfunction "ADC1_DM1_K2") (pintype "input"))
    )
    (net (code "105") (name "Net-(TP19-TP)") (class "Default")
      (node (ref "TP19") (pin "1") (pinfunction "TP_1") (pintype "passive"))
      (node (ref "U24") (pin "L1") (pinfunction "PGA0_DP_L1") (pintype "input"))
    )
    (net (code "106") (name "Net-(TP20-TP)") (class "Default")
      (node (ref "TP20") (pin "1") (pinfunction "TP_1") (pintype "passive"))
      (node (ref "U24") (pin "L2") (pinfunction "PGA0_DM_L2") (pintype "input"))
    )
    (net (code "107") (name "Net-(TP21-TP)") (class "Default")
      (node (ref "TP21") (pin "1") (pinfunction "TP_1") (pintype "passive"))
      (node (ref "U24") (pin "M1") (pinfunction "PGA1_DP_M1") (pintype "input"))
    )
    (net (code "108") (name "Net-(TP22-TP)") (class "Default")
      (node (ref "TP22") (pin "1") (pinfunction "TP_1") (pintype "passive"))
      (node (ref "U24") (pin "M2") (pinfunction "PGA1_DM_M2") (pintype "input"))
    )
    (net (code "109") (name "Net-(U24-ADC0_SE8{slash}ADC1_SE8)") (class "Default")
      (node (ref "C84") (pin "2") (pinfunction "2_2") (pintype "passive"))
      (node (ref "R57") (pin "2") (pinfunction "2_2") (pintype "passive"))
      (node (ref "U24") (pin "H10") (pinfunction "ADC0_SE8/ADC1_SE8_H10") (pintype "bidirectional"))
    )
    (net (code "110") (name "Net-(U24-ADC0_SE9{slash}ADC1_SE9)") (class "Default")
      (node (ref "C85") (pin "2") (pinfunction "2_2") (pintype "passive"))
      (node (ref "R58") (pin "2") (pinfunction "2_2") (pintype "passive"))
      (node (ref "U24") (pin "H9") (pinfunction "ADC0_SE9/ADC1_SE9_H9") (pintype "bidirectional"))
    )
    (net (code "111") (name "Net-(U24-ADC0_SE12)") (class "Default")
      (node (ref "C86") (pin "2") (pinfunction "2_2") (pintype "passive"))
      (node (ref "R59") (pin "2") (pinfunction "2_2") (pintype "passive"))
      (node (ref "U24") (pin "G12") (pinfunction "ADC0_SE12_G12") (pintype "bidirectional"))
    )
    (net (code "112") (name "Net-(U24-ADC0_SE13)") (class "Default")
      (node (ref "C87") (pin "2") (pinfunction "2_2") (pintype "passive"))
      (node (ref "R60") (pin "2") (pinfunction "2_2") (pintype "passive"))
      (node (ref "U24") (pin "G11") (pinfunction "ADC0_SE13_G11") (pintype "bidirectional"))
    )
    (net (code "113") (name "Net-(U24-ADC0_SE16)") (class "Default")
      (node (ref "C81") (pin "2") (pinfunction "2_2") (pintype "passive"))
      (node (ref "R54") (pin "2") (pinfunction "2_2") (pintype "passive"))
      (node (ref "U24") (pin "J3") (pinfunction "ADC0_SE16_J3") (pintype "input"))
    )
    (net (code "114") (name "Net-(U24-ADC0_SE17{slash}PTE24)") (class "Default")
      (node (ref "C82") (pin "2") (pinfunction "2_2") (pintype "passive"))
      (node (ref "R55") (pin "2") (pinfunction "2_2") (pintype "passive"))
      (node (ref "U24") (pin "M4") (pinfunction "ADC0_SE17/PTE24_M4") (pintype "input"))
    )
    (net (code "115") (name "Net-(U24-ADC0_SE18{slash}PTE25)") (class "Default")
      (node (ref "C83") (pin "2") (pinfunction "2_2") (pintype "passive"))
      (node (ref "R56") (pin "2") (pinfunction "2_2") (pintype "passive"))
      (node (ref "U24") (pin "K5") (pinfunction "ADC0_SE18/PTE25_K5") (pintype "input"))
    )
    (net (code "116") (name "Net-(U24-ADC1_SE10)") (class "Default")
      (node (ref "C88") (pin "2") (pinfunction "2_2") (pintype "passive"))
      (node (ref "R61") (pin "2") (pinfunction "2_2") (pintype "passive"))
      (node (ref "U24") (pin "G10") (pinfunction "ADC1_SE10_G10") (pintype "bidirectional"))
    )
    (net (code "117") (name "Net-(U24-ADC1_SE11)") (class "Default")
      (node (ref "C89") (pin "2") (pinfunction "2_2") (pintype "passive"))
      (node (ref "R62") (pin "2") (pinfunction "2_2") (pintype "passive"))
      (node (ref "U24") (pin "G9") (pinfunction "ADC1_SE11_G9") (pintype "bidirectional"))
    )
    (net (code "118") (name "Net-(U24-ADC1_SE16)") (class "Default")
      (node (ref "C80") (pin "2") (pinfunction "2_2") (pintype "passive"))
      (node (ref "R53") (pin "2") (pinfunction "2_2") (pintype "passive"))
      (node (ref "U24") (pin "K3") (pinfunction "ADC1_SE16_K3") (pintype "input"))
    )
    (net (code "119") (name "Net-(U24-EXTAL32)") (class "Default")
      (node (ref "C92") (pin "2") (pinfunction "2_2") (pintype "passive"))
      (node (ref "R69") (pin "2") (pinfunction "2_2") (pintype "passive"))
      (node (ref "U24") (pin "M6") (pinfunction "EXTAL32_M6") (pintype "input"))
      (node (ref "Y1") (pin "1") (pinfunction "1_1") (pintype "passive"))
    )
    (net (code "120") (name "Net-(U24-FB_CLKOUT)") (class "Default")
      (node (ref "R174") (pin "2") (pinfunction "2_2") (pintype "passive"))
      (node (ref "U24") (pin "A11") (pinfunction "FB_CLKOUT_A11") (pintype "output"))
    )
    (net (code "121") (name "Net-(U24-I2C0_SCL{slash}PTD8)") (class "Default")
      (node (ref "J13") (pin "2") (pinfunction "2_2") (pintype "passive"))
      (node (ref "U24") (pin "C9") (pinfunction "I2C0_SCL/PTD8_C9") (pintype "bidirectional"))
    )
    (net (code "122") (name "Net-(U24-I2C0_SDA{slash}PTD9)") (class "Default")
      (node (ref "J13") (pin "3") (pinfunction "3_3") (pintype "passive"))
      (node (ref "U24") (pin "B9") (pinfunction "I2C0_SDA/PTD9_B9") (pintype "bidirectional"))
    )
    (net (code "123") (name "Net-(U24-JTAG_TCLK{slash}EZP_CLK)") (class "Default")
      (node (ref "J14") (pin "4") (pinfunction "4_4") (pintype "passive"))
      (node (ref "R65") (pin "2") (pinfunction "2_2") (pintype "passive"))
      (node (ref "U24") (pin "J5") (pinfunction "JTAG_TCLK/EZP_CLK_J5") (pintype "bidirectional"))
    )
    (net (code "124") (name "Net-(U24-JTAG_TDI{slash}EZP_DI)") (class "Default")
      (node (ref "J14") (pin "8") (pinfunction "8_8") (pintype "passive"))
      (node (ref "R64") (pin "2") (pinfunction "2_2") (pintype "passive"))
      (node (ref "U24") (pin "J6") (pinfunction "JTAG_TDI/EZP_DI_J6") (pintype "bidirectional"))
    )
    (net (code "125") (name "Net-(U24-JTAG_TDO{slash}EZP_DO)") (class "Default")
      (node (ref "J14") (pin "6") (pinfunction "6_6") (pintype "passive"))
      (node (ref "U24") (pin "K6") (pinfunction "JTAG_TDO/EZP_DO_K6") (pintype "bidirectional"))
    )
    (net (code "126") (name "Net-(U24-JTAG_TMS)") (class "Default")
      (node (ref "J14") (pin "2") (pinfunction "2_2") (pintype "passive"))
      (node (ref "R66") (pin "2") (pinfunction "2_2") (pintype "passive"))
      (node (ref "U24") (pin "K7") (pinfunction "JTAG_TMS_K7") (pintype "bidirectional"))
    )
    (net (code "127") (name "Net-(U24-PTD7)") (class "Default")
      (node (ref "J13") (pin "1") (pinfunction "1_1") (pintype "passive"))
      (node (ref "U24") (pin "A1") (pinfunction "PTD7_A1") (pintype "bidirectional"))
    )
    (net (code "128") (name "Net-(U24-PTD10)") (class "Default")
      (node (ref "J13") (pin "4") (pinfunction "4_4") (pintype "passive"))
      (node (ref "U24") (pin "B3") (pinfunction "PTD10_B3") (pintype "bidirectional"))
    )
    (net (code "129") (name "Net-(U24-TRACE_CLKOUT)") (class "Default")
      (node (ref "J14") (pin "12") (pinfunction "12_12") (pintype "passive"))
      (node (ref "U24") (pin "J7") (pinfunction "TRACE_CLKOUT_J7") (pintype "bidirectional"))
    )
    (net (code "130") (name "Net-(U24-TRACE_D0)") (class "Default")
      (node (ref "J14") (pin "14") (pinfunction "14_14") (pintype "passive"))
      (node (ref "U24") (pin "M9") (pinfunction "TRACE_D0_M9") (pintype "bidirectional"))
    )
    (net (code "131") (name "Net-(U24-TRACE_D1)") (class "Default")
      (node (ref "J14") (pin "16") (pinfunction "16_16") (pintype "passive"))
      (node (ref "U24") (pin "L8") (pinfunction "TRACE_D1_L8") (pintype "bidirectional"))
    )
    (net (code "132") (name "Net-(U24-TRACE_D2)") (class "Default")
      (node (ref "J14") (pin "18") (pinfunction "18_18") (pintype "passive"))
      (node (ref "U24") (pin "K8") (pinfunction "TRACE_D2_K8") (pintype "bidirectional"))
    )
    (net (code "133") (name "Net-(U24-TRACE_D3)") (class "Default")
      (node (ref "J14") (pin "20") (pinfunction "20_20") (pintype "passive"))
      (node (ref "U24") (pin "J8") (pinfunction "TRACE_D3_J8") (pintype "bidirectional"))
    )
    (net (code "134") (name "Net-(U24-VREFH)") (class "Default")
      (node (ref "C76") (pin "1") (pinfunction "1_1") (pintype "passive"))
      (node (ref "L2") (pin "2") (pinfunction "2_2") (pintype "passive"))
      (node (ref "U24") (pin "G5") (pinfunction "VREFH_G5") (pintype "passive"))
    )
    (net (code "135") (name "Net-(U24-VREFOUT)") (class "Default")
      (node (ref "C78") (pin "2") (pinfunction "2_2") (pintype "passive"))
      (node (ref "U24") (pin "M3") (pinfunction "VREFOUT_M3") (pintype "output"))
    )
    (net (code "136") (name "Net-(U24-XTAL32)") (class "Default")
      (node (ref "C91") (pin "2") (pinfunction "2_2") (pintype "passive"))
      (node (ref "R69") (pin "1") (pinfunction "1_1") (pintype "passive"))
      (node (ref "U24") (pin "M7") (pinfunction "XTAL32_M7") (pintype "output"))
      (node (ref "Y1") (pin "4") (pinfunction "4_4") (pintype "passive"))
    )
    (net (code "137") (name "unconnected-(J13-Pad5)") (class "Default")
      (node (ref "J13") (pin "5") (pinfunction "5_5") (pintype "passive"))
    )
    (net (code "138") (name "unconnected-(J14-Pad11)") (class "Default")
      (node (ref "J14") (pin "11") (pinfunction "11_11") (pintype "passive"))
    )
    (net (code "139") (name "unconnected-(J14-Pad13)") (class "Default")
      (node (ref "J14") (pin "13") (pinfunction "13_13") (pintype "passive"))
    )
    (net (code "140") (name "unconnected-(U24-SPI2_PCS1{slash}PTD15-PadC1)") (class "Default")
      (node (ref "U24") (pin "C1") (pinfunction "SPI2_PCS1/PTD15_C1") (pintype "bidirectional"))
    )
    (net (code "141") (name "unconnected-(U24-XTAL-PadM11)") (class "Default")
      (node (ref "U24") (pin "M11") (pinfunction "XTAL_M11") (pintype "output"))
    )
    (net (code "142") (name "unconnected-(U25-OE-Pad1)") (class "Default")
      (node (ref "U25") (pin "1") (pinfunction "OE_1") (pintype "input"))
    )
  )
)
